# 7segement2digits1badidea-mk-5_1.net
KiCad netlist of a schematic drawn in EAGLE
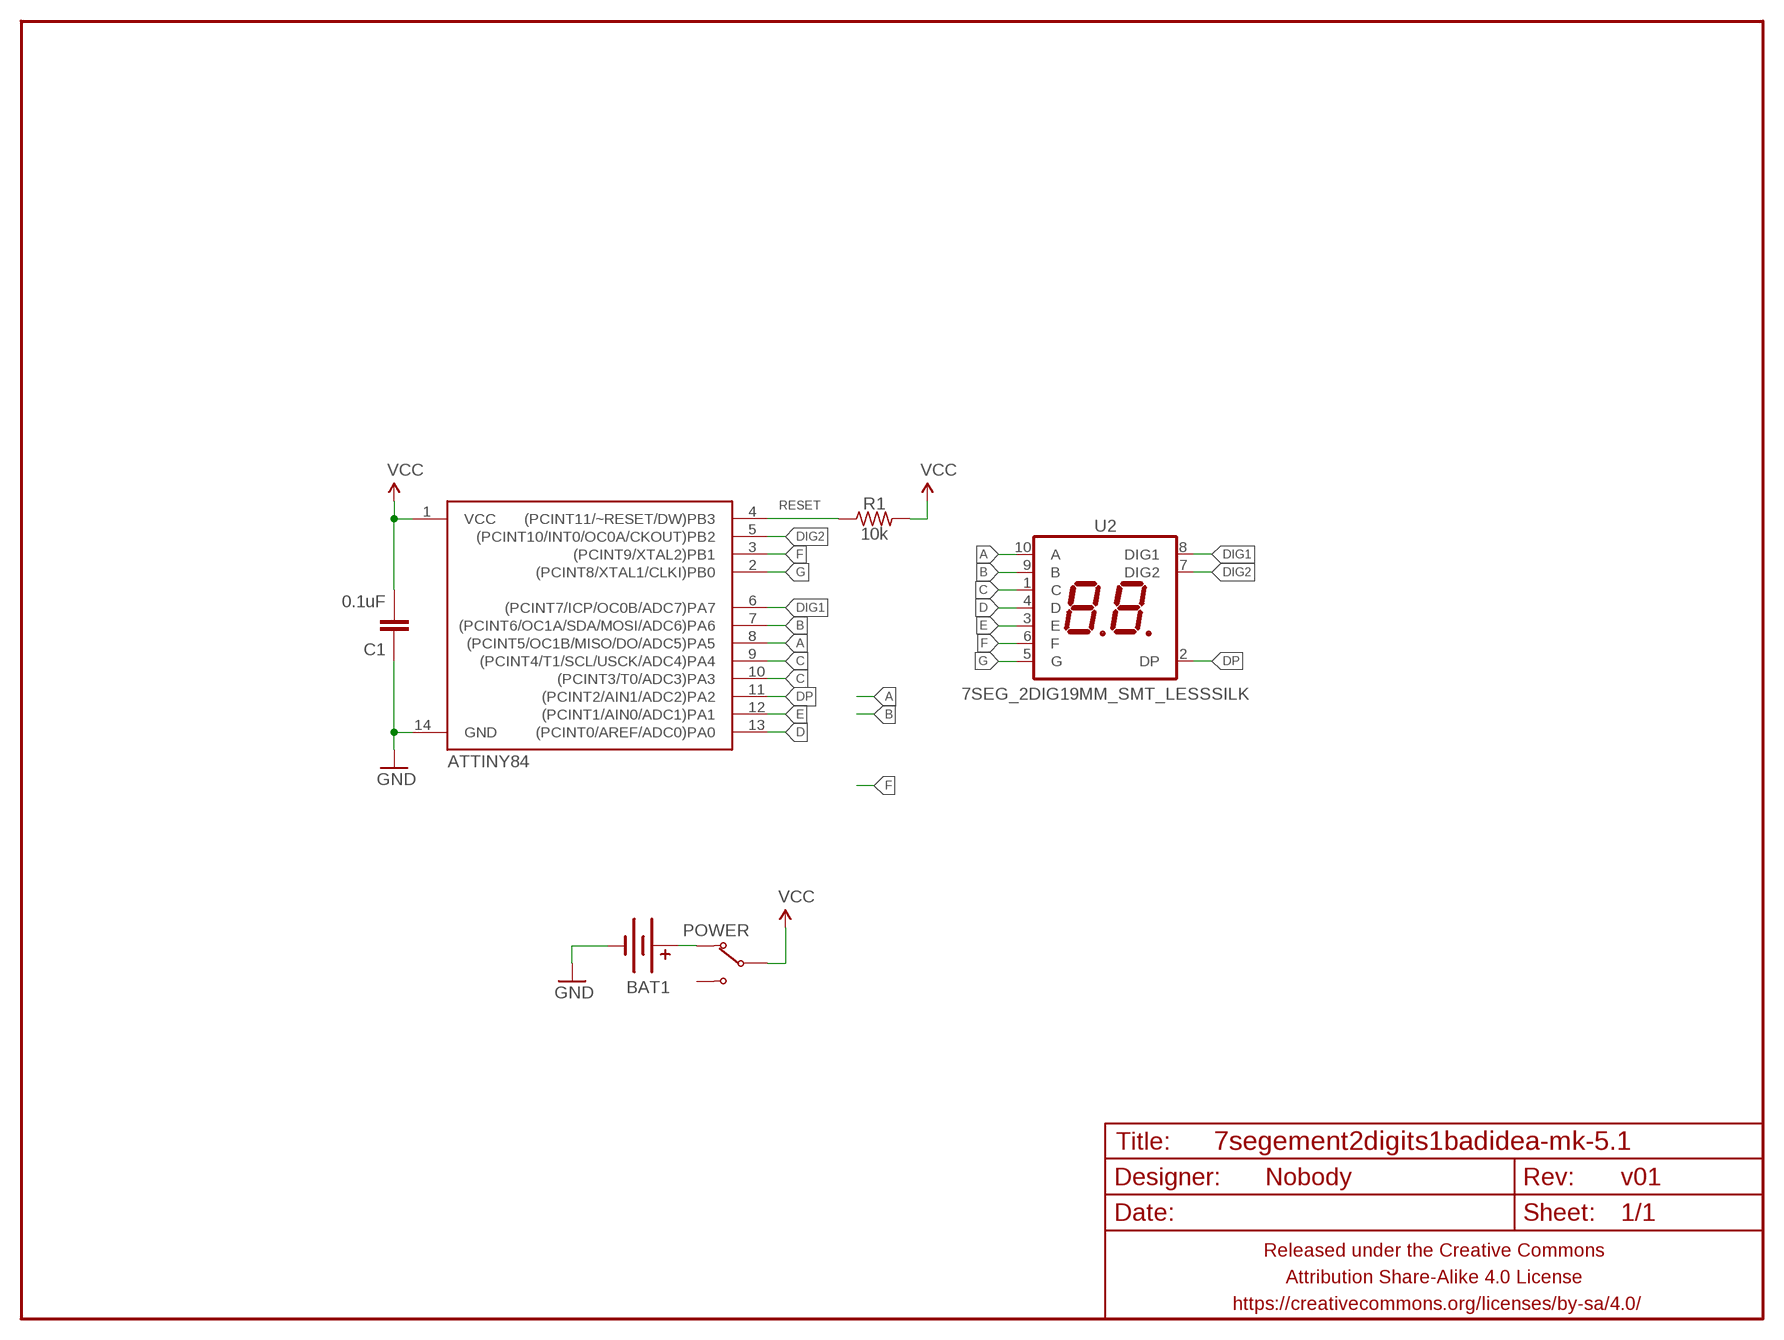
[diagram p0: schematic, sheet 1]

(export (version "E")
  (design (tool "Eeschema 10.0.6"))
  (components
    (comp (ref "BAT1")
      (value "BATTERY20MM_SMD_TIGHT")
      (footprint "eagle-import:BATTCON_20MM_MINE_STAHPIT")
      (libsource (lib "eagle-import") (part "BATTERY20MM_SMD_TIGHT"))
    )
    (comp (ref "C1")
      (value "0.1uF")
      (footprint "eagle-import:C0805")
      (libsource (lib "eagle-import") (part "CAPACITOR-CERAMICC0805"))
    )
    (comp (ref "FRAME1")
      (value "FRAME-LETTERNO_PACKAGE")
      (footprint "eagle-import:DUMMY")
      (fields (field (name "DESIGNER") "Nobody"))
      (libsource (lib "eagle-import") (part "FRAME-LETTERNO_PACKAGE"))
    )
    (comp (ref "POWER")
      (value "SWITCH-SPDTPTH-RA-2.54MM")
      (footprint "eagle-import:SPDT-RA-2.54MM")
      (libsource (lib "eagle-import") (part "SWITCH-SPDTPTH-RA-2.54MM"))
    )
    (comp (ref "R1")
      (value "10k")
      (footprint "eagle-import:R0805")
      (libsource (lib "eagle-import") (part "RESISTORR0805"))
    )
    (comp (ref "U1")
      (value "ATTINY84")
      (footprint "eagle-import:SO14")
      (libsource (lib "eagle-import") (part "ATTINY84"))
    )
    (comp (ref "U2")
      (value "7SEG_2DIG19MM_SMT_LESSSILK")
      (footprint "eagle-import:7SEG_2DIG_19MM_SMT_LESSSILK")
      (libsource (lib "eagle-import") (part "7SEG_2DIG19MM_SMT_LESSSILK"))
    )
  )
  (nets
    (net (code "1") (name "/RESET") (class "Default")
      (node (ref "R1") (pin "1") (pinfunction "1_1") (pintype "passive"))
      (node (ref "U1") (pin "4") (pinfunction "(PCINT11/~{RESET/DW})PB3_4") (pintype "bidirectional"))
    )
    (net (code "2") (name "A") (class "Default")
      (node (ref "U1") (pin "8") (pinfunction "(PCINT5/OC1B/MISO/DO/ADC5)PA5_8") (pintype "bidirectional"))
      (node (ref "U2") (pin "10") (pinfunction "A_10") (pintype "passive"))
    )
    (net (code "3") (name "B") (class "Default")
      (node (ref "U1") (pin "7") (pinfunction "(PCINT6/OC1A/SDA/MOSI/ADC6)PA6_7") (pintype "bidirectional"))
      (node (ref "U2") (pin "9") (pinfunction "B_9") (pintype "passive"))
    )
    (net (code "4") (name "C") (class "Default")
      (node (ref "U1") (pin "10") (pinfunction "(PCINT3/T0/ADC3)PA3_10") (pintype "bidirectional"))
      (node (ref "U1") (pin "9") (pinfunction "(PCINT4/T1/SCL/USCK/ADC4)PA4_9") (pintype "bidirectional"))
      (node (ref "U2") (pin "1") (pinfunction "C_1") (pintype "passive"))
    )
    (net (code "5") (name "D") (class "Default")
      (node (ref "U1") (pin "13") (pinfunction "(PCINT0/AREF/ADC0)PA0_13") (pintype "bidirectional"))
      (node (ref "U2") (pin "4") (pinfunction "D_4") (pintype "passive"))
    )
    (net (code "6") (name "DIG1") (class "Default")
      (node (ref "U1") (pin "6") (pinfunction "(PCINT7/ICP/OC0B/ADC7)PA7_6") (pintype "bidirectional"))
      (node (ref "U2") (pin "8") (pinfunction "DIG1_8") (pintype "passive"))
    )
    (net (code "7") (name "DIG2") (class "Default")
      (node (ref "U1") (pin "5") (pinfunction "(PCINT10/INT0/OC0A/CKOUT)PB2_5") (pintype "bidirectional"))
      (node (ref "U2") (pin "7") (pinfunction "DIG2_7") (pintype "passive"))
    )
    (net (code "8") (name "DP") (class "Default")
      (node (ref "U1") (pin "11") (pinfunction "(PCINT2/AIN1/ADC2)PA2_11") (pintype "bidirectional"))
      (node (ref "U2") (pin "2") (pinfunction "DP_2") (pintype "passive"))
    )
    (net (code "9") (name "E") (class "Default")
      (node (ref "U1") (pin "12") (pinfunction "(PCINT1/AIN0/ADC1)PA1_12") (pintype "bidirectional"))
      (node (ref "U2") (pin "3") (pinfunction "E_3") (pintype "passive"))
    )
    (net (code "10") (name "F") (class "Default")
      (node (ref "U1") (pin "3") (pinfunction "(PCINT9/XTAL2)PB1_3") (pintype "bidirectional"))
      (node (ref "U2") (pin "6") (pinfunction "F_6") (pintype "passive"))
    )
    (net (code "11") (name "G") (class "Default")
      (node (ref "U1") (pin "2") (pinfunction "(PCINT8/XTAL1/CLKI)PB0_2") (pintype "bidirectional"))
      (node (ref "U2") (pin "5") (pinfunction "G_5") (pintype "passive"))
    )
    (net (code "12") (name "GND") (class "Default")
      (node (ref "BAT1") (pin "BOTTOM") (pinfunction "-_BOTTOM") (pintype "power_in"))
      (node (ref "C1") (pin "1") (pinfunction "1_1") (pintype "passive"))
      (node (ref "U1") (pin "14") (pinfunction "GND_14") (pintype "bidirectional"))
    )
    (net (code "13") (name "Net-(POWER-NC)") (class "Default")
      (node (ref "BAT1") (pin "TOP@1") (pinfunction "+_TOP@1") (pintype "power_in"))
      (node (ref "BAT1") (pin "TOP@2") (pinfunction "+_TOP@2") (pintype "power_in"))
      (node (ref "POWER") (pin "1") (pinfunction "NC_1") (pintype "passive"))
    )
    (net (code "14") (name "VCC") (class "Default")
      (node (ref "C1") (pin "2") (pinfunction "2_2") (pintype "passive"))
      (node (ref "POWER") (pin "2") (pinfunction "COM_2") (pintype "passive"))
      (node (ref "R1") (pin "2") (pinfunction "2_2") (pintype "passive"))
      (node (ref "U1") (pin "1") (pinfunction "VCC_1") (pintype "bidirectional"))
    )
    (net (code "15") (name "unconnected-(POWER-NO-Pad3)") (class "Default")
      (node (ref "POWER") (pin "3") (pinfunction "NO_3") (pintype "passive"))
    )
  )
)
